# flight_comp_v2.net
KiCad netlist of a schematic drawn in EAGLE
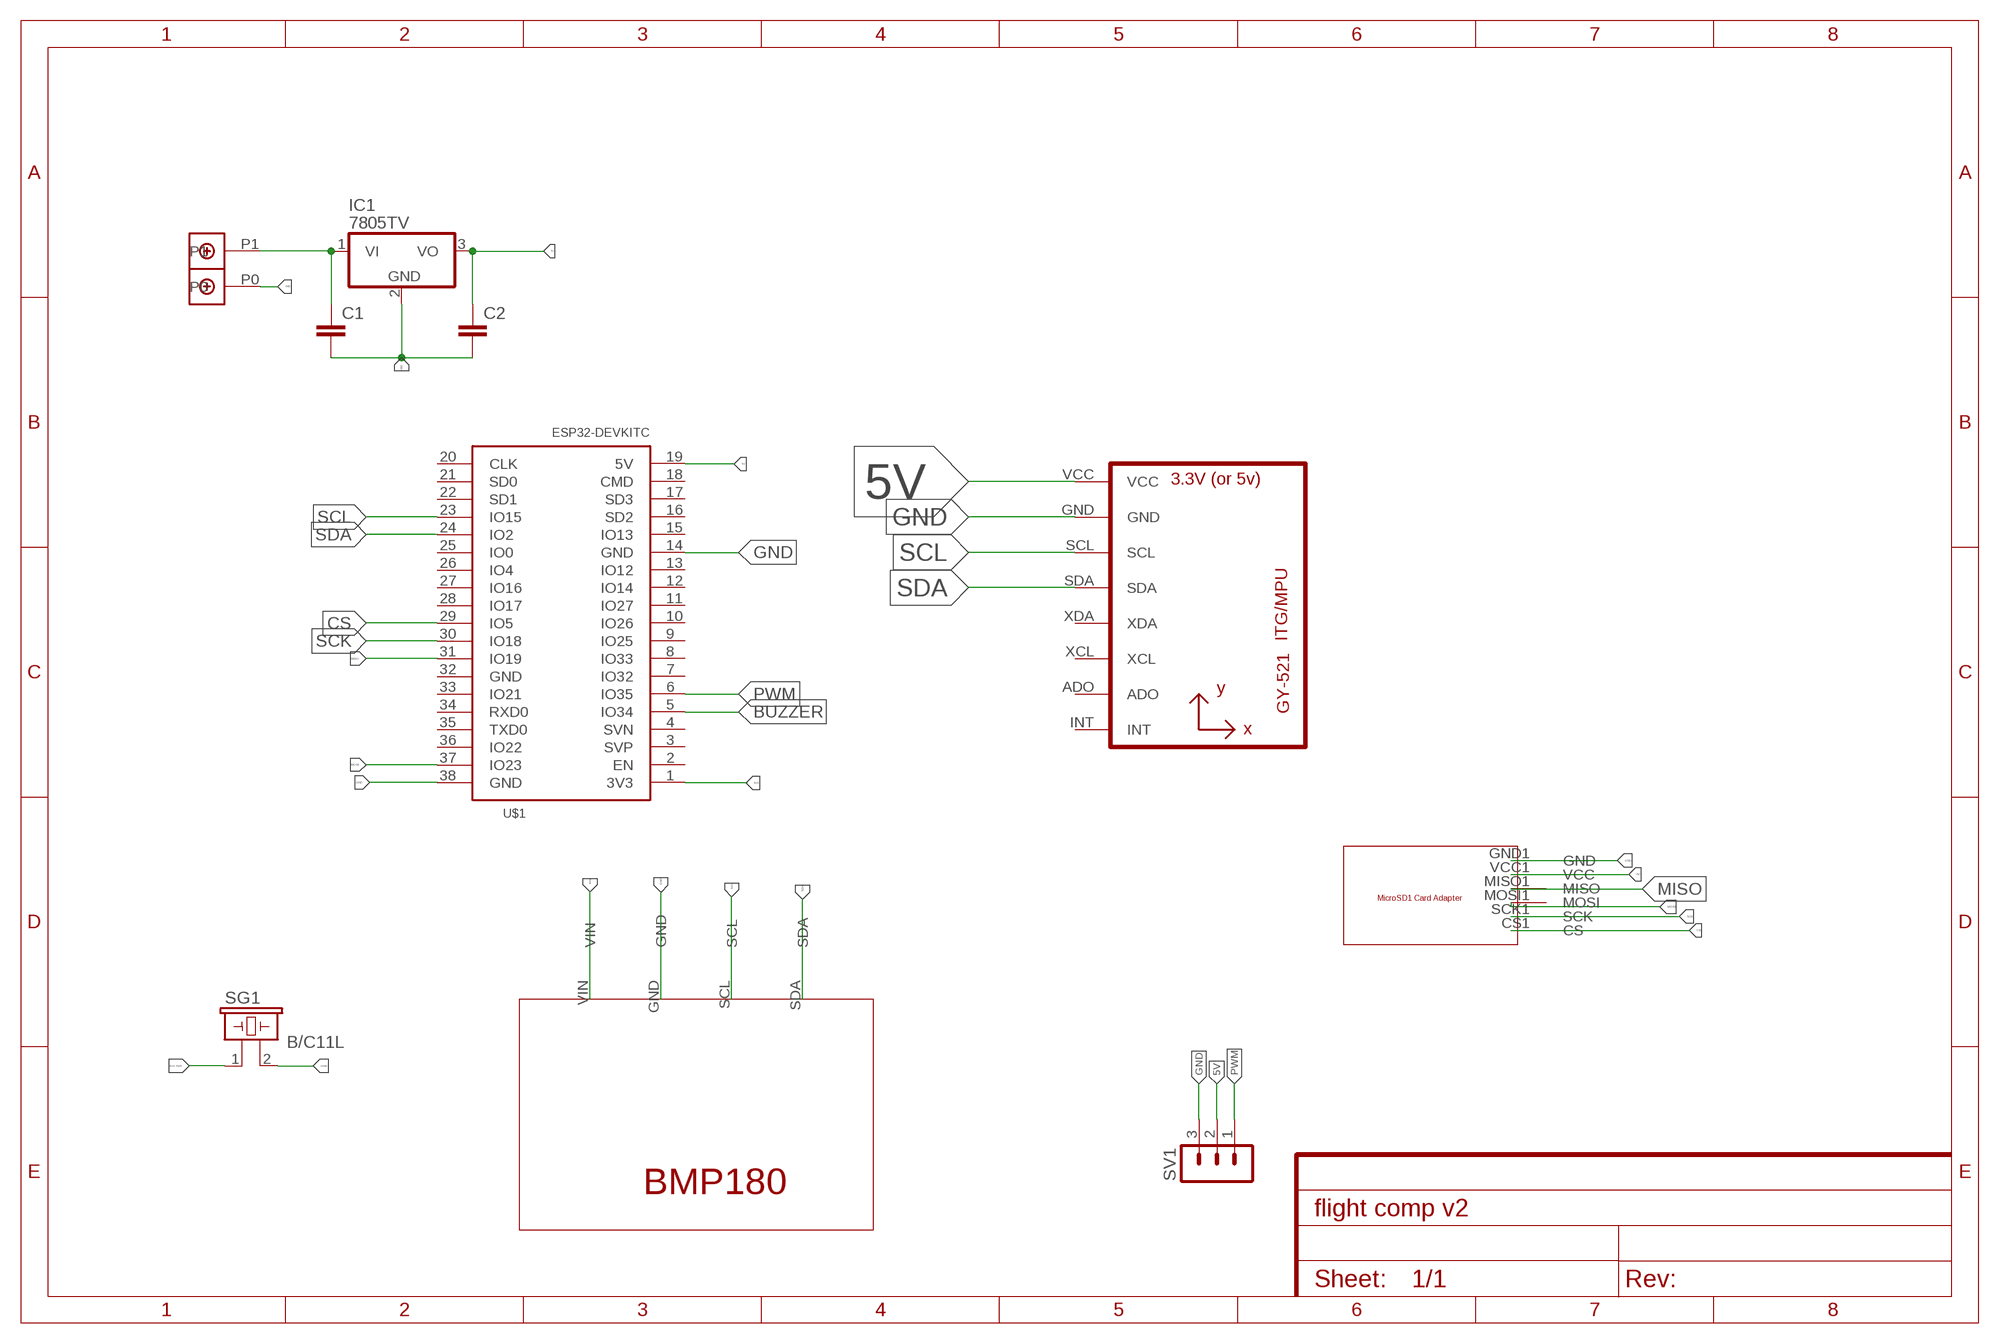
[diagram p0: schematic, sheet 1]

(export (version "E")
  (design (tool "Eeschema 10.0.6"))
  (components
    (comp (ref "C1")
      (value "C2,5-3")
      (footprint "eagle-import:C2.5-3")
      (libsource (lib "eagle-import") (part "C2,5-3"))
    )
    (comp (ref "C2")
      (value "C2,5-3")
      (footprint "eagle-import:C2.5-3")
      (libsource (lib "eagle-import") (part "C2,5-3"))
    )
    (comp (ref "IC1")
      (value "7805TV")
      (footprint "eagle-import:TO220V")
      (libsource (lib "eagle-import") (part "78TV05"))
    )
    (comp (ref "SG1")
      (value "B/C11L")
      (footprint "eagle-import:B_C11L")
      (libsource (lib "eagle-import") (part "B/C11L"))
    )
    (comp (ref "SV1")
      (value "MA03-1")
      (footprint "eagle-import:MA03-1")
      (libsource (lib "eagle-import") (part "MA03-1"))
    )
    (comp (ref "U$1")
      (value "ESP32DEVKITC")
      (footprint "eagle-import:ESP32-DEVKITC")
      (libsource (lib "eagle-import") (part "ESP32DEVKITC"))
    )
    (comp (ref "U$2")
      (value "MICROSDADAPTER")
      (footprint "eagle-import:MICROSDADAPTER")
      (libsource (lib "eagle-import") (part "MICROSDADAPTER"))
    )
    (comp (ref "U$3")
      (value "BMP180")
      (footprint "eagle-import:BMP180")
      (libsource (lib "eagle-import") (part "BMP180"))
    )
    (comp (ref "U$4")
      (value "DBCONN-1X2")
      (footprint "eagle-import:DBCONN-1X2")
      (libsource (lib "eagle-import") (part "DBCONN-1X2"))
    )
    (comp (ref "U1")
      (value "GY-521MPU6050")
      (footprint "eagle-import:GY-521")
      (libsource (lib "eagle-import") (part "GY-521MPU6050"))
    )
  )
  (nets
    (net (code "1") (name "3V3") (class "Default")
      (node (ref "U$1") (pin "1") (pinfunction "3V3_1") (pintype "bidirectional"))
      (node (ref "U$3") (pin "VIN") (pinfunction "VIN_VIN") (pintype "bidirectional"))
    )
    (net (code "2") (name "5V") (class "Default")
      (node (ref "C2") (pin "1") (pinfunction "1_1") (pintype "passive"))
      (node (ref "IC1") (pin "3") (pinfunction "VO_3") (pintype "passive"))
      (node (ref "SV1") (pin "2") (pinfunction "2_2") (pintype "passive"))
      (node (ref "U$1") (pin "19") (pinfunction "5V_19") (pintype "bidirectional"))
      (node (ref "U$2") (pin "VCC1") (pinfunction "VCC_VCC1") (pintype "bidirectional"))
      (node (ref "U1") (pin "VCC") (pinfunction "VCC_VCC") (pintype "bidirectional"))
    )
    (net (code "3") (name "BUZZER") (class "Default")
      (node (ref "SG1") (pin "1") (pinfunction "1_1") (pintype "passive"))
      (node (ref "U$1") (pin "5") (pinfunction "IO34_5") (pintype "bidirectional"))
    )
    (net (code "4") (name "CS") (class "Default")
      (node (ref "U$1") (pin "29") (pinfunction "IO5_29") (pintype "bidirectional"))
      (node (ref "U$2") (pin "CS1") (pinfunction "CS_CS1") (pintype "bidirectional"))
    )
    (net (code "5") (name "GND") (class "Default")
      (node (ref "C1") (pin "2") (pinfunction "2_2") (pintype "passive"))
      (node (ref "C2") (pin "2") (pinfunction "2_2") (pintype "passive"))
      (node (ref "IC1") (pin "2") (pinfunction "GND_2") (pintype "passive"))
      (node (ref "SG1") (pin "2") (pinfunction "2_2") (pintype "passive"))
      (node (ref "SV1") (pin "3") (pinfunction "3_3") (pintype "passive"))
      (node (ref "U$1") (pin "14") (pinfunction "GND_14") (pintype "bidirectional"))
      (node (ref "U$1") (pin "38") (pinfunction "GND_38") (pintype "bidirectional"))
      (node (ref "U$2") (pin "GND1") (pinfunction "GND_GND1") (pintype "bidirectional"))
      (node (ref "U$3") (pin "GND") (pinfunction "GND_GND") (pintype "bidirectional"))
      (node (ref "U$4") (pin "P0") (pinfunction "P0_P0") (pintype "bidirectional"))
      (node (ref "U1") (pin "GND") (pinfunction "GND_GND") (pintype "bidirectional"))
    )
    (net (code "6") (name "MISO") (class "Default")
      (node (ref "U$1") (pin "31") (pinfunction "IO19_31") (pintype "bidirectional"))
      (node (ref "U$2") (pin "MISO1") (pinfunction "MISO_MISO1") (pintype "bidirectional"))
    )
    (net (code "7") (name "MOSI") (class "Default")
      (node (ref "U$1") (pin "37") (pinfunction "IO23_37") (pintype "bidirectional"))
      (node (ref "U$2") (pin "MOSI1") (pinfunction "MOSI_MOSI1") (pintype "bidirectional"))
    )
    (net (code "8") (name "Net-(IC1-VI)") (class "Default")
      (node (ref "C1") (pin "1") (pinfunction "1_1") (pintype "passive"))
      (node (ref "IC1") (pin "1") (pinfunction "VI_1") (pintype "input"))
      (node (ref "U$4") (pin "P1") (pinfunction "P1_P1") (pintype "bidirectional"))
    )
    (net (code "9") (name "PWM") (class "Default")
      (node (ref "SV1") (pin "1") (pinfunction "1_1") (pintype "passive"))
      (node (ref "U$1") (pin "6") (pinfunction "IO35_6") (pintype "bidirectional"))
    )
    (net (code "10") (name "SCK") (class "Default")
      (node (ref "U$1") (pin "30") (pinfunction "IO18_30") (pintype "bidirectional"))
      (node (ref "U$2") (pin "SCK1") (pinfunction "SCK_SCK1") (pintype "bidirectional"))
    )
    (net (code "11") (name "SCL") (class "Default")
      (node (ref "U$1") (pin "23") (pinfunction "IO15_23") (pintype "bidirectional"))
      (node (ref "U$3") (pin "SCL") (pinfunction "SCL_SCL") (pintype "bidirectional"))
      (node (ref "U1") (pin "SCL") (pinfunction "SCL_SCL") (pintype "bidirectional"))
    )
    (net (code "12") (name "SDA") (class "Default")
      (node (ref "U$1") (pin "24") (pinfunction "IO2_24") (pintype "bidirectional"))
      (node (ref "U$3") (pin "SDA") (pinfunction "SDA_SDA") (pintype "bidirectional"))
      (node (ref "U1") (pin "SDA") (pinfunction "SDA_SDA") (pintype "bidirectional"))
    )
    (net (code "13") (name "unconnected-(U$1-CLK-Pad20)") (class "Default")
      (node (ref "U$1") (pin "20") (pinfunction "CLK_20") (pintype "bidirectional"))
    )
    (net (code "14") (name "unconnected-(U$1-CMD-Pad18)") (class "Default")
      (node (ref "U$1") (pin "18") (pinfunction "CMD_18") (pintype "bidirectional"))
    )
    (net (code "15") (name "unconnected-(U$1-EN-Pad2)") (class "Default")
      (node (ref "U$1") (pin "2") (pinfunction "EN_2") (pintype "bidirectional"))
    )
    (net (code "16") (name "unconnected-(U$1-GND-Pad32)") (class "Default")
      (node (ref "U$1") (pin "32") (pinfunction "GND_32") (pintype "bidirectional"))
    )
    (net (code "17") (name "unconnected-(U$1-IO0-Pad25)") (class "Default")
      (node (ref "U$1") (pin "25") (pinfunction "IO0_25") (pintype "bidirectional"))
    )
    (net (code "18") (name "unconnected-(U$1-IO4-Pad26)") (class "Default")
      (node (ref "U$1") (pin "26") (pinfunction "IO4_26") (pintype "bidirectional"))
    )
    (net (code "19") (name "unconnected-(U$1-IO12-Pad13)") (class "Default")
      (node (ref "U$1") (pin "13") (pinfunction "IO12_13") (pintype "bidirectional"))
    )
    (net (code "20") (name "unconnected-(U$1-IO13-Pad15)") (class "Default")
      (node (ref "U$1") (pin "15") (pinfunction "IO13_15") (pintype "bidirectional"))
    )
    (net (code "21") (name "unconnected-(U$1-IO14-Pad12)") (class "Default")
      (node (ref "U$1") (pin "12") (pinfunction "IO14_12") (pintype "bidirectional"))
    )
    (net (code "22") (name "unconnected-(U$1-IO16-Pad27)") (class "Default")
      (node (ref "U$1") (pin "27") (pinfunction "IO16_27") (pintype "bidirectional"))
    )
    (net (code "23") (name "unconnected-(U$1-IO17-Pad28)") (class "Default")
      (node (ref "U$1") (pin "28") (pinfunction "IO17_28") (pintype "bidirectional"))
    )
    (net (code "24") (name "unconnected-(U$1-IO21-Pad33)") (class "Default")
      (node (ref "U$1") (pin "33") (pinfunction "IO21_33") (pintype "bidirectional"))
    )
    (net (code "25") (name "unconnected-(U$1-IO22-Pad36)") (class "Default")
      (node (ref "U$1") (pin "36") (pinfunction "IO22_36") (pintype "bidirectional"))
    )
    (net (code "26") (name "unconnected-(U$1-IO25-Pad9)") (class "Default")
      (node (ref "U$1") (pin "9") (pinfunction "IO25_9") (pintype "bidirectional"))
    )
    (net (code "27") (name "unconnected-(U$1-IO26-Pad10)") (class "Default")
      (node (ref "U$1") (pin "10") (pinfunction "IO26_10") (pintype "bidirectional"))
    )
    (net (code "28") (name "unconnected-(U$1-IO27-Pad11)") (class "Default")
      (node (ref "U$1") (pin "11") (pinfunction "IO27_11") (pintype "bidirectional"))
    )
    (net (code "29") (name "unconnected-(U$1-IO32-Pad7)") (class "Default")
      (node (ref "U$1") (pin "7") (pinfunction "IO32_7") (pintype "bidirectional"))
    )
    (net (code "30") (name "unconnected-(U$1-IO33-Pad8)") (class "Default")
      (node (ref "U$1") (pin "8") (pinfunction "IO33_8") (pintype "bidirectional"))
    )
    (net (code "31") (name "unconnected-(U$1-RXD0-Pad34)") (class "Default")
      (node (ref "U$1") (pin "34") (pinfunction "RXD0_34") (pintype "bidirectional"))
    )
    (net (code "32") (name "unconnected-(U$1-SD0-Pad21)") (class "Default")
      (node (ref "U$1") (pin "21") (pinfunction "SD0_21") (pintype "bidirectional"))
    )
    (net (code "33") (name "unconnected-(U$1-SD1-Pad22)") (class "Default")
      (node (ref "U$1") (pin "22") (pinfunction "SD1_22") (pintype "bidirectional"))
    )
    (net (code "34") (name "unconnected-(U$1-SD2-Pad16)") (class "Default")
      (node (ref "U$1") (pin "16") (pinfunction "SD2_16") (pintype "bidirectional"))
    )
    (net (code "35") (name "unconnected-(U$1-SD3-Pad17)") (class "Default")
      (node (ref "U$1") (pin "17") (pinfunction "SD3_17") (pintype "bidirectional"))
    )
    (net (code "36") (name "unconnected-(U$1-SVN-Pad4)") (class "Default")
      (node (ref "U$1") (pin "4") (pinfunction "SVN_4") (pintype "bidirectional"))
    )
    (net (code "37") (name "unconnected-(U$1-SVP-Pad3)") (class "Default")
      (node (ref "U$1") (pin "3") (pinfunction "SVP_3") (pintype "bidirectional"))
    )
    (net (code "38") (name "unconnected-(U$1-TXD0-Pad35)") (class "Default")
      (node (ref "U$1") (pin "35") (pinfunction "TXD0_35") (pintype "bidirectional"))
    )
    (net (code "39") (name "unconnected-(U1-PadADO)") (class "Default")
      (node (ref "U1") (pin "ADO") (pinfunction "ADO_ADO") (pintype "bidirectional"))
    )
    (net (code "40") (name "unconnected-(U1-PadINT)") (class "Default")
      (node (ref "U1") (pin "INT") (pinfunction "INT_INT") (pintype "bidirectional"))
    )
    (net (code "41") (name "unconnected-(U1-PadXCL)") (class "Default")
      (node (ref "U1") (pin "XCL") (pinfunction "XCL_XCL") (pintype "bidirectional"))
    )
    (net (code "42") (name "unconnected-(U1-PadXDA)") (class "Default")
      (node (ref "U1") (pin "XDA") (pinfunction "XDA_XDA") (pintype "bidirectional"))
    )
  )
)
